# design.net
KiCad netlist of a schematic drawn in Altium Designer
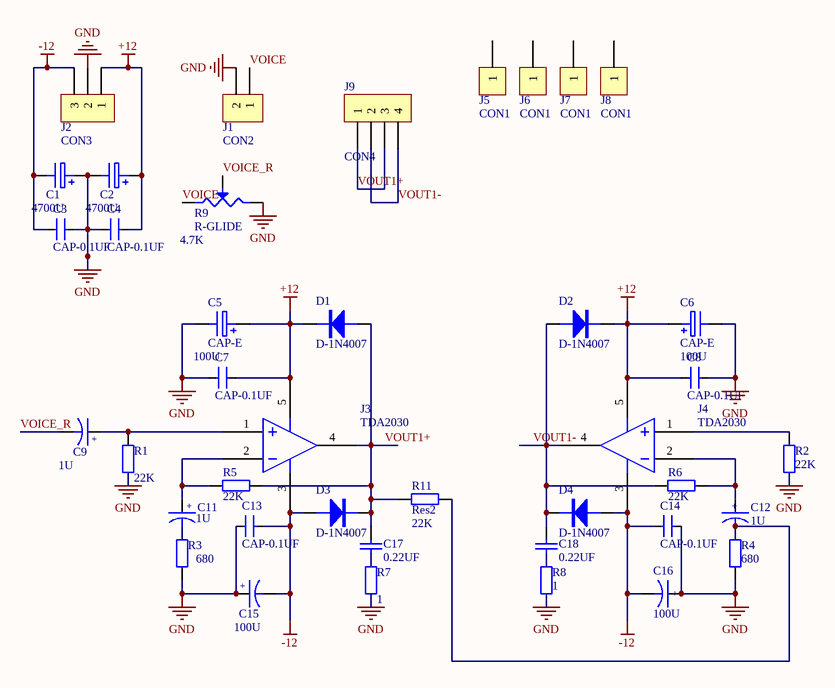
[diagram p0: 功放.SchDoc]

(export (version "E")
  (design (tool "Eeschema 10.0.6"))
  (components
    (comp (ref "C1")
      (value "4700U")
      (footprint "4700U/35V")
      (description "电解电容")
      (fields (field (name "Comment") "CAP-E"))
      (libsource (lib "gf-sch") (part "CAP-E"))
    )
    (comp (ref "C2")
      (value "4700U")
      (footprint "4700U/35V")
      (description "电解电容")
      (fields (field (name "Comment") "CAP-E"))
      (libsource (lib "gf-sch") (part "CAP-E"))
    )
    (comp (ref "C3")
      (value "CAP-0.1UF")
      (footprint "0805C")
      (description "SMD-CAP")
      (libsource (lib "gf-sch") (part "CAP-0.1UF"))
    )
    (comp (ref "C4")
      (value "CAP-0.1UF")
      (footprint "0805C")
      (description "SMD-CAP")
      (libsource (lib "gf-sch") (part "CAP-0.1UF"))
    )
    (comp (ref "C5")
      (value "CAP-E")
      (footprint "3528C")
      (description "电解电容")
      (fields (field (name "ALTIUM_VALUE") "100U"))
      (libsource (lib "gf-sch") (part "CAP-E"))
    )
    (comp (ref "C6")
      (value "CAP-E")
      (footprint "3528C")
      (description "电解电容")
      (fields (field (name "ALTIUM_VALUE") "100U"))
      (libsource (lib "gf-sch") (part "CAP-E"))
    )
    (comp (ref "C7")
      (value "CAP-0.1UF")
      (footprint "0805C")
      (description "SMD-CAP")
      (libsource (lib "gf-sch") (part "CAP-0.1UF"))
    )
    (comp (ref "C8")
      (value "CAP-0.1UF")
      (footprint "0805C")
      (description "SMD-CAP")
      (libsource (lib "gf-sch") (part "CAP-0.1UF"))
    )
    (comp (ref "C9")
      (value "1U")
      (footprint "C3216")
      (description "钽电容")
      (fields (field (name "Comment") "CAP-T"))
      (libsource (lib "") (part "CAP-T_1"))
    )
    (comp (ref "C11")
      (value "1U")
      (footprint "C3216")
      (description "钽电容")
      (fields (field (name "Comment") "CAP-T"))
      (libsource (lib "") (part "CAP-T_1"))
    )
    (comp (ref "C12")
      (value "1U")
      (footprint "C3216")
      (description "钽电容")
      (fields (field (name "Comment") "CAP-T"))
      (libsource (lib "gf-sch") (part "CAP-T"))
    )
    (comp (ref "C13")
      (value "CAP-0.1UF")
      (footprint "0805C")
      (description "SMD-CAP")
      (libsource (lib "gf-sch") (part "CAP-0.1UF"))
    )
    (comp (ref "C14")
      (value "CAP-0.1UF")
      (footprint "0805C")
      (description "SMD-CAP")
      (libsource (lib "gf-sch") (part "CAP-0.1UF"))
    )
    (comp (ref "C15")
      (value "100U")
      (footprint "C3216")
      (description "钽电容")
      (fields (field (name "Comment") "CAP-T"))
      (libsource (lib "") (part "CAP-T_1"))
    )
    (comp (ref "C16")
      (value "100U")
      (footprint "C3216")
      (description "钽电容")
      (fields (field (name "Comment") "CAP-T"))
      (libsource (lib "gf-sch") (part "CAP-T"))
    )
    (comp (ref "C17")
      (value "0.22UF")
      (footprint "RAD-0.3")
      (description "Capacitor")
      (fields (field (name "Comment") "Cap") (field (name "PUBLISHER") "Altium Limited"))
      (libsource (lib "Miscellaneous Devices") (part "Cap"))
    )
    (comp (ref "C18")
      (value "0.22UF")
      (footprint "RAD-0.3")
      (description "Capacitor")
      (fields (field (name "Comment") "Cap") (field (name "PUBLISHER") "Altium Limited"))
      (libsource (lib "Miscellaneous Devices") (part "Cap"))
    )
    (comp (ref "D1")
      (value "D-1N4007")
      (footprint "M7")
      (description "Diode")
      (libsource (lib "gf-sch") (part "D-1N4007"))
    )
    (comp (ref "D2")
      (value "D-1N4007")
      (footprint "M7")
      (description "Diode")
      (libsource (lib "") (part "D-1N4007_2"))
    )
    (comp (ref "D3")
      (value "D-1N4007")
      (footprint "M7")
      (description "Diode")
      (libsource (lib "") (part "D-1N4007_1"))
    )
    (comp (ref "D4")
      (value "D-1N4007")
      (footprint "M7")
      (description "Diode")
      (libsource (lib "") (part "D-1N4007_3"))
    )
    (comp (ref "J1")
      (value "CON2")
      (footprint "VOICE-1")
      (description "Connector")
      (libsource (lib "gf-sch") (part "CON2"))
    )
    (comp (ref "J2")
      (value "CON3")
      (footprint "POWER-1")
      (description "Connector")
      (libsource (lib "gf-sch") (part "CON3"))
    )
    (comp (ref "J3") (value "TDA2030") (footprint "TDA2030") (libsource (lib "gf-sch") (part "TDA2030")))
    (comp (ref "J4") (value "TDA2030") (footprint "TDA2030") (libsource (lib "gf-sch") (part "TDA2030")))
    (comp (ref "J5")
      (value "CON1")
      (footprint "GDK")
      (description "Connector")
      (libsource (lib "mian") (part "CON1"))
    )
    (comp (ref "J6")
      (value "CON1")
      (footprint "GDK")
      (description "Connector")
      (libsource (lib "mian") (part "CON1"))
    )
    (comp (ref "J7")
      (value "CON1")
      (footprint "GDK")
      (description "Connector")
      (libsource (lib "mian") (part "CON1"))
    )
    (comp (ref "J8")
      (value "CON1")
      (footprint "GDK")
      (description "Connector")
      (libsource (lib "mian") (part "CON1"))
    )
    (comp (ref "J9")
      (value "CON4")
      (footprint "HB-95-4")
      (description "Connector")
      (libsource (lib "gf-sch") (part "CON4"))
    )
    (comp (ref "R1")
      (value "22K")
      (footprint "0805R")
      (description "Resistor")
      (fields (field (name "Comment") "Res2") (field (name "PUBLISHER") "Altium Limited"))
      (libsource (lib "") (part "Res2_2"))
    )
    (comp (ref "R2")
      (value "22K")
      (footprint "0805R")
      (description "Resistor")
      (fields (field (name "Comment") "Res2") (field (name "PUBLISHER") "Altium Limited"))
      (libsource (lib "Miscellaneous Devices") (part "Res2"))
    )
    (comp (ref "R3")
      (value "680")
      (footprint "0805R")
      (description "Resistor")
      (fields (field (name "Comment") "Res2") (field (name "PUBLISHER") "Altium Limited"))
      (libsource (lib "Miscellaneous Devices") (part "Res2"))
    )
    (comp (ref "R4")
      (value "680")
      (footprint "0805R")
      (description "Resistor")
      (fields (field (name "Comment") "Res2") (field (name "PUBLISHER") "Altium Limited"))
      (libsource (lib "") (part "Res2_2"))
    )
    (comp (ref "R5")
      (value "22K")
      (footprint "0805R")
      (description "Resistor")
      (fields (field (name "Comment") "Res2") (field (name "PUBLISHER") "Altium Limited"))
      (libsource (lib "") (part "Res2_1"))
    )
    (comp (ref "R6")
      (value "22K")
      (footprint "0805R")
      (description "Resistor")
      (fields (field (name "Comment") "Res2") (field (name "PUBLISHER") "Altium Limited"))
      (libsource (lib "Miscellaneous Devices") (part "Res2"))
    )
    (comp (ref "R7")
      (value "1")
      (footprint "0805R")
      (description "Resistor")
      (fields (field (name "Comment") "Res2") (field (name "PUBLISHER") "Altium Limited"))
      (libsource (lib "Miscellaneous Devices") (part "Res2"))
    )
    (comp (ref "R8")
      (value "1")
      (footprint "0805R")
      (description "Resistor")
      (fields (field (name "Comment") "Res2") (field (name "PUBLISHER") "Altium Limited"))
      (libsource (lib "") (part "Res2_2"))
    )
    (comp (ref "R9")
      (value "R-GLIDE")
      (footprint "RV09-5")
      (fields (field (name "ALTIUM_VALUE") "4.7K"))
      (libsource (lib "gf-sch") (part "R-GLIDE"))
    )
    (comp (ref "R11")
      (value "Res2")
      (footprint "0805R")
      (description "Resistor")
      (fields (field (name "ALTIUM_VALUE") "22K") (field (name "PUBLISHER") "Altium Limited"))
      (libsource (lib "") (part "Res2_2"))
    )
  )
  (nets
    (net (code "1") (name "+12") (class "Default")
      (node (ref "C2") (pin "1") (pinfunction "1_1") (pintype "passive"))
      (node (ref "C4") (pin "2") (pinfunction "2_2") (pintype "passive"))
      (node (ref "C5") (pin "1") (pinfunction "1_1") (pintype "passive"))
      (node (ref "C6") (pin "1") (pinfunction "1_1") (pintype "passive"))
      (node (ref "C7") (pin "2") (pinfunction "2_2") (pintype "passive"))
      (node (ref "C8") (pin "2") (pinfunction "2_2") (pintype "passive"))
      (node (ref "D1") (pin "2") (pinfunction "2_2") (pintype "passive"))
      (node (ref "D2") (pin "2") (pinfunction "2_2") (pintype "passive"))
      (node (ref "J2") (pin "1") (pinfunction "1_1") (pintype "passive"))
      (node (ref "J3") (pin "5") (pinfunction "5_5") (pintype "passive"))
      (node (ref "J4") (pin "5") (pinfunction "5_5") (pintype "passive"))
    )
    (net (code "2") (name "-12") (class "Default")
      (node (ref "C1") (pin "2") (pinfunction "2_2") (pintype "passive"))
      (node (ref "C13") (pin "2") (pinfunction "2_2") (pintype "passive"))
      (node (ref "C14") (pin "2") (pinfunction "2_2") (pintype "passive"))
      (node (ref "C15") (pin "2") (pinfunction "2_2") (pintype "passive"))
      (node (ref "C16") (pin "2") (pinfunction "2_2") (pintype "passive"))
      (node (ref "C3") (pin "2") (pinfunction "2_2") (pintype "passive"))
      (node (ref "D3") (pin "1") (pinfunction "1_1") (pintype "passive"))
      (node (ref "D4") (pin "1") (pinfunction "1_1") (pintype "passive"))
      (node (ref "J2") (pin "3") (pinfunction "3_3") (pintype "passive"))
      (node (ref "J3") (pin "3") (pinfunction "3_3") (pintype "passive"))
      (node (ref "J4") (pin "3") (pinfunction "3_3") (pintype "passive"))
    )
    (net (code "3") (name "/VOICE") (class "Default")
      (node (ref "J1") (pin "1") (pinfunction "1_1") (pintype "passive"))
      (node (ref "R9") (pin "1") (pinfunction "1_1") (pintype "passive"))
    )
    (net (code "4") (name "/VOICE_R") (class "Default")
      (node (ref "C9") (pin "2") (pinfunction "2_2") (pintype "passive"))
      (node (ref "R9") (pin "3") (pinfunction "W_3") (pintype "passive"))
    )
    (net (code "5") (name "/VOUT1+") (class "Default")
      (node (ref "C17") (pin "2") (pinfunction "2_2") (pintype "passive"))
      (node (ref "D1") (pin "1") (pinfunction "1_1") (pintype "passive"))
      (node (ref "D3") (pin "2") (pinfunction "2_2") (pintype "passive"))
      (node (ref "J3") (pin "4") (pinfunction "4_4") (pintype "passive"))
      (node (ref "J9") (pin "1") (pinfunction "1_1") (pintype "passive"))
      (node (ref "J9") (pin "3") (pinfunction "3_3") (pintype "passive"))
      (node (ref "R11") (pin "1") (pinfunction "1_1") (pintype "passive"))
      (node (ref "R5") (pin "1") (pinfunction "1_1") (pintype "passive"))
    )
    (net (code "6") (name "/VOUT1-") (class "Default")
      (node (ref "C18") (pin "2") (pinfunction "2_2") (pintype "passive"))
      (node (ref "D2") (pin "1") (pinfunction "1_1") (pintype "passive"))
      (node (ref "D4") (pin "2") (pinfunction "2_2") (pintype "passive"))
      (node (ref "J4") (pin "4") (pinfunction "4_4") (pintype "passive"))
      (node (ref "J9") (pin "2") (pinfunction "2_2") (pintype "passive"))
      (node (ref "J9") (pin "4") (pinfunction "4_4") (pintype "passive"))
      (node (ref "R6") (pin "1") (pinfunction "1_1") (pintype "passive"))
    )
    (net (code "7") (name "GND") (class "Default")
      (node (ref "C1") (pin "1") (pinfunction "1_1") (pintype "passive"))
      (node (ref "C13") (pin "1") (pinfunction "1_1") (pintype "passive"))
      (node (ref "C14") (pin "1") (pinfunction "1_1") (pintype "passive"))
      (node (ref "C15") (pin "1") (pinfunction "1_1") (pintype "passive"))
      (node (ref "C16") (pin "1") (pinfunction "1_1") (pintype "passive"))
      (node (ref "C2") (pin "2") (pinfunction "2_2") (pintype "passive"))
      (node (ref "C3") (pin "1") (pinfunction "1_1") (pintype "passive"))
      (node (ref "C4") (pin "1") (pinfunction "1_1") (pintype "passive"))
      (node (ref "C5") (pin "2") (pinfunction "2_2") (pintype "passive"))
      (node (ref "C6") (pin "2") (pinfunction "2_2") (pintype "passive"))
      (node (ref "C7") (pin "1") (pinfunction "1_1") (pintype "passive"))
      (node (ref "C8") (pin "1") (pinfunction "1_1") (pintype "passive"))
      (node (ref "J1") (pin "2") (pinfunction "2_2") (pintype "passive"))
      (node (ref "J2") (pin "2") (pinfunction "2_2") (pintype "passive"))
      (node (ref "R1") (pin "1") (pinfunction "1_1") (pintype "passive"))
      (node (ref "R2") (pin "1") (pinfunction "1_1") (pintype "passive"))
      (node (ref "R3") (pin "1") (pinfunction "1_1") (pintype "passive"))
      (node (ref "R4") (pin "1") (pinfunction "1_1") (pintype "passive"))
      (node (ref "R7") (pin "1") (pinfunction "1_1") (pintype "passive"))
      (node (ref "R8") (pin "1") (pinfunction "1_1") (pintype "passive"))
      (node (ref "R9") (pin "2") (pinfunction "2_2") (pintype "passive"))
    )
    (net (code "8") (name "Net-(C9-Pad1)") (class "Default")
      (node (ref "C9") (pin "1") (pinfunction "1_1") (pintype "passive"))
      (node (ref "J3") (pin "1") (pinfunction "1_1") (pintype "passive"))
      (node (ref "R1") (pin "2") (pinfunction "2_2") (pintype "passive"))
    )
    (net (code "9") (name "Net-(C11-Pad1)") (class "Default")
      (node (ref "C11") (pin "1") (pinfunction "1_1") (pintype "passive"))
      (node (ref "J3") (pin "2") (pintype "passive"))
      (node (ref "R5") (pin "2") (pinfunction "2_2") (pintype "passive"))
    )
    (net (code "10") (name "Net-(C11-Pad2)") (class "Default")
      (node (ref "C11") (pin "2") (pinfunction "2_2") (pintype "passive"))
      (node (ref "R3") (pin "2") (pinfunction "2_2") (pintype "passive"))
    )
    (net (code "11") (name "Net-(C12-Pad1)") (class "Default")
      (node (ref "C12") (pin "1") (pinfunction "1_1") (pintype "passive"))
      (node (ref "J4") (pin "2") (pintype "passive"))
      (node (ref "R6") (pin "2") (pinfunction "2_2") (pintype "passive"))
    )
    (net (code "12") (name "Net-(C12-Pad2)") (class "Default")
      (node (ref "C12") (pin "2") (pinfunction "2_2") (pintype "passive"))
      (node (ref "R11") (pin "2") (pinfunction "2_2") (pintype "passive"))
      (node (ref "R4") (pin "2") (pinfunction "2_2") (pintype "passive"))
    )
    (net (code "13") (name "Net-(C17-Pad1)") (class "Default")
      (node (ref "C17") (pin "1") (pinfunction "1_1") (pintype "passive"))
      (node (ref "R7") (pin "2") (pinfunction "2_2") (pintype "passive"))
    )
    (net (code "14") (name "Net-(C18-Pad1)") (class "Default")
      (node (ref "C18") (pin "1") (pinfunction "1_1") (pintype "passive"))
      (node (ref "R8") (pin "2") (pinfunction "2_2") (pintype "passive"))
    )
    (net (code "15") (name "Net-(J4-Pad1)") (class "Default")
      (node (ref "J4") (pin "1") (pinfunction "1_1") (pintype "passive"))
      (node (ref "R2") (pin "2") (pinfunction "2_2") (pintype "passive"))
    )
    (net (code "16") (name "unconnected-(J5-Pad1)") (class "Default")
      (node (ref "J5") (pin "1") (pinfunction "1_1") (pintype "passive"))
    )
    (net (code "17") (name "unconnected-(J6-Pad1)") (class "Default")
      (node (ref "J6") (pin "1") (pinfunction "1_1") (pintype "passive"))
    )
    (net (code "18") (name "unconnected-(J7-Pad1)") (class "Default")
      (node (ref "J7") (pin "1") (pinfunction "1_1") (pintype "passive"))
    )
    (net (code "19") (name "unconnected-(J8-Pad1)") (class "Default")
      (node (ref "J8") (pin "1") (pinfunction "1_1") (pintype "passive"))
    )
  )
)
